# 4aw.net
KiCad netlist of a schematic drawn in EAGLE
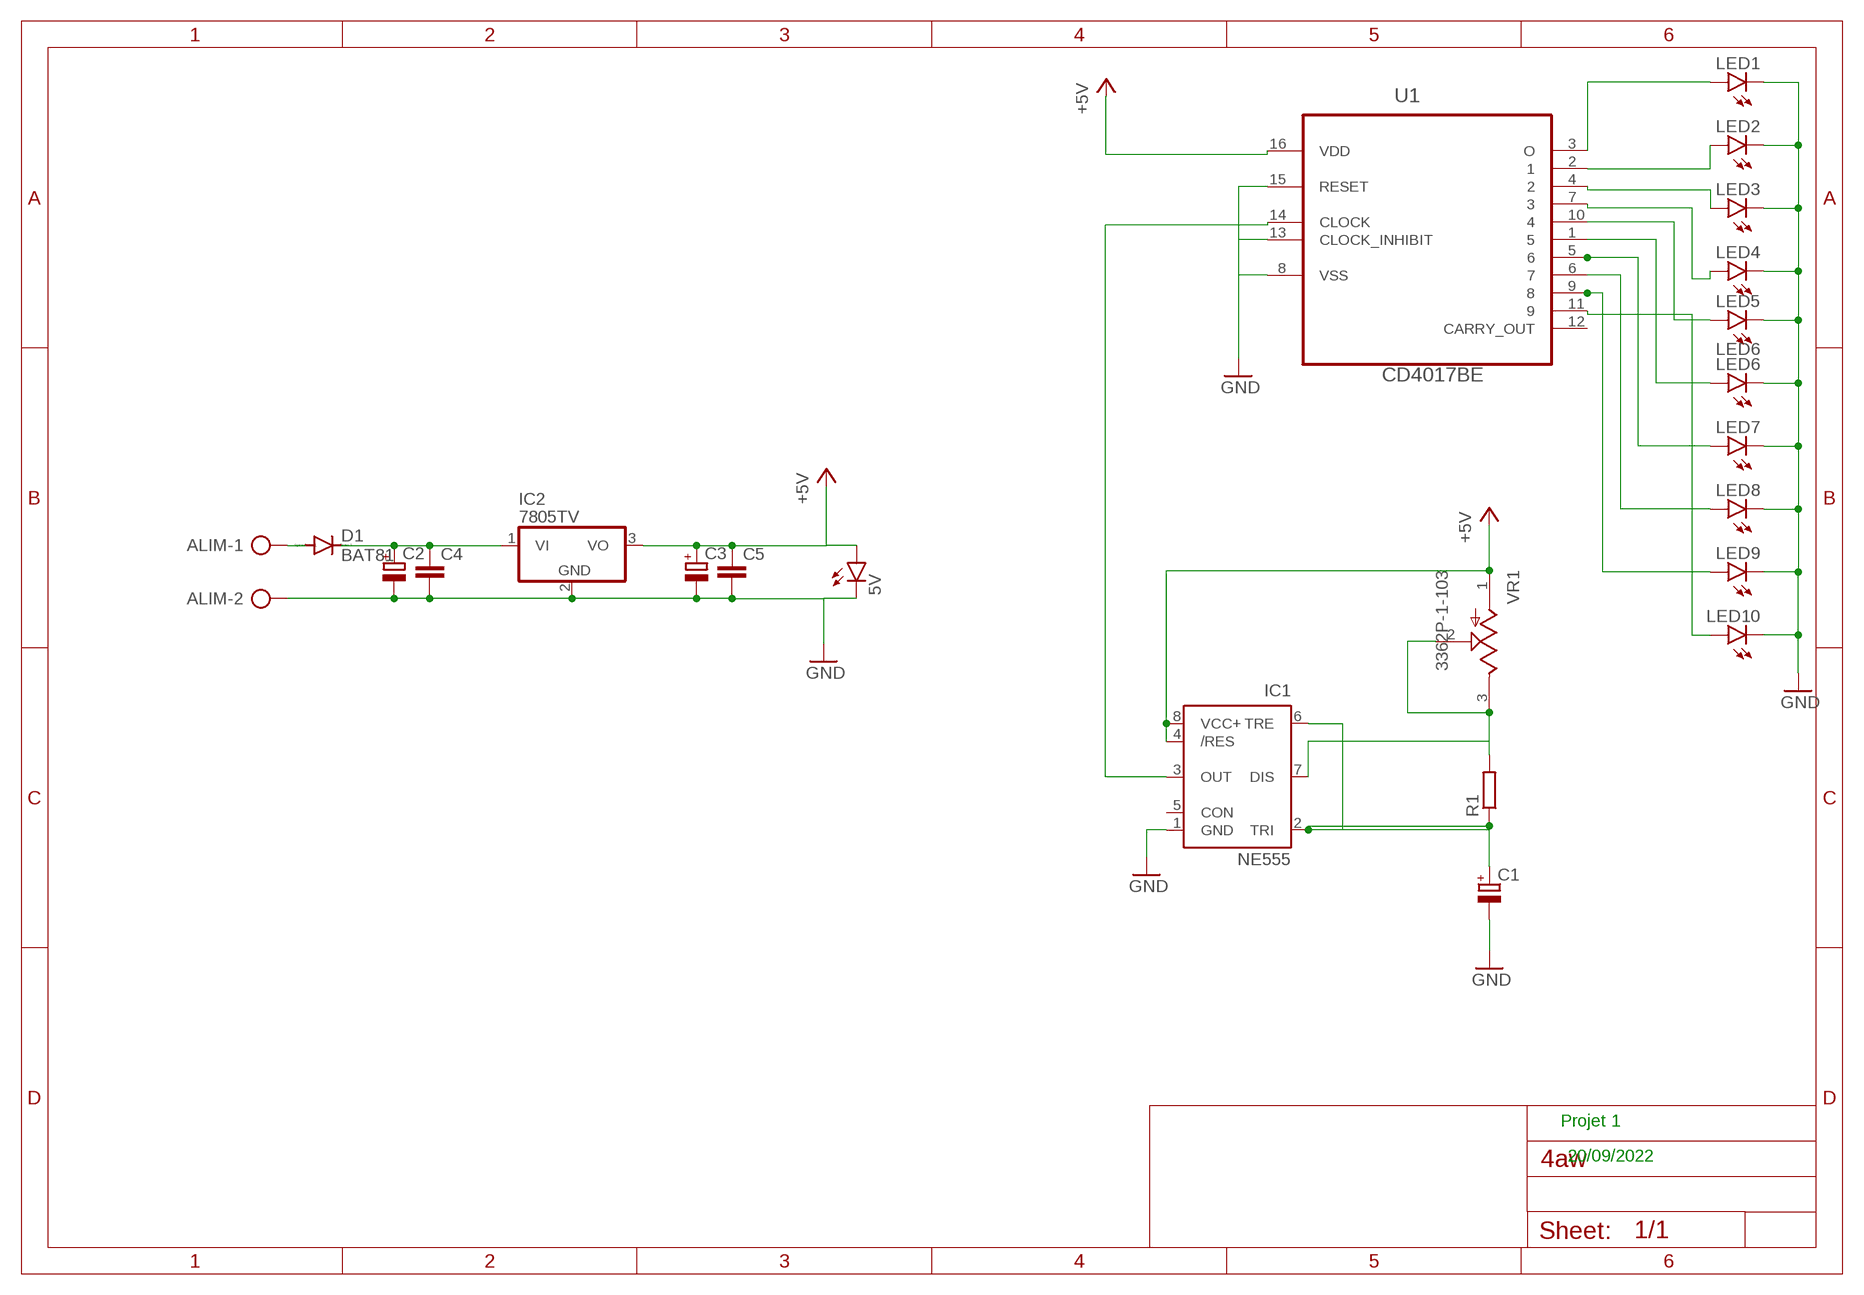
[diagram p0: schematic, sheet 1]

(export (version "E")
  (design (tool "Eeschema 10.0.6"))
  (components
    (comp (ref "5V")
      (value "LED3MM")
      (footprint "eagle-import:LED3MM")
      (libsource (lib "eagle-import") (part "LED3MM"))
    )
    (comp (ref "ALIM")
      (value "AK500/2")
      (footprint "eagle-import:AK500_2")
      (libsource (lib "eagle-import") (part "AK500/2"))
    )
    (comp (ref "C1")
      (value "CPOL-EUE2.5-5")
      (footprint "eagle-import:E2,5-5")
      (libsource (lib "eagle-import") (part "resistor_348_CPOL-EUE2.5-5"))
    )
    (comp (ref "C2")
      (value "CPOL-EUE2.5-5")
      (footprint "eagle-import:E2,5-5")
      (libsource (lib "eagle-import") (part "CPOL-EUE2.5-5"))
    )
    (comp (ref "C3")
      (value "CPOL-EUE2.5-5")
      (footprint "eagle-import:E2,5-5")
      (libsource (lib "eagle-import") (part "CPOL-EUE2.5-5"))
    )
    (comp (ref "C4")
      (value "C-EU050-024X044")
      (footprint "eagle-import:C050-024X044")
      (libsource (lib "eagle-import") (part "C-EU050-024X044"))
    )
    (comp (ref "C5")
      (value "C-EU050-024X044")
      (footprint "eagle-import:C050-024X044")
      (libsource (lib "eagle-import") (part "C-EU050-024X044"))
    )
    (comp (ref "D1")
      (value "BAT81")
      (footprint "eagle-import:DO34-7")
      (libsource (lib "eagle-import") (part "BAT81"))
    )
    (comp (ref "IC1")
      (value "NE555")
      (footprint "eagle-import:DIL-08")
      (fields (field (name "MF") "Arrow Electronics") (field (name "MPN") "NE555N"))
      (libsource (lib "eagle-import") (part "NE555"))
    )
    (comp (ref "IC2")
      (value "7805TV")
      (footprint "eagle-import:TO220V")
      (libsource (lib "eagle-import") (part "78TV05"))
    )
    (comp (ref "LED1")
      (value "LED5MM")
      (footprint "eagle-import:LED5MM")
      (libsource (lib "eagle-import") (part "LED5MM"))
    )
    (comp (ref "LED2")
      (value "LED5MM")
      (footprint "eagle-import:LED5MM")
      (libsource (lib "eagle-import") (part "LED5MM"))
    )
    (comp (ref "LED3")
      (value "LED5MM")
      (footprint "eagle-import:LED5MM")
      (libsource (lib "eagle-import") (part "LED5MM"))
    )
    (comp (ref "LED4")
      (value "LED5MM")
      (footprint "eagle-import:LED5MM")
      (libsource (lib "eagle-import") (part "LED5MM"))
    )
    (comp (ref "LED5")
      (value "LED5MM")
      (footprint "eagle-import:LED5MM")
      (libsource (lib "eagle-import") (part "LED5MM"))
    )
    (comp (ref "LED6")
      (value "LED6")
      (footprint "eagle-import:LED5MM")
      (libsource (lib "eagle-import") (part "LED5MM"))
    )
    (comp (ref "LED7")
      (value "LED5MM")
      (footprint "eagle-import:LED5MM")
      (libsource (lib "eagle-import") (part "LED5MM"))
    )
    (comp (ref "LED8")
      (value "LED5MM")
      (footprint "eagle-import:LED5MM")
      (libsource (lib "eagle-import") (part "LED5MM"))
    )
    (comp (ref "LED9")
      (value "LED5MM")
      (footprint "eagle-import:LED5MM")
      (libsource (lib "eagle-import") (part "LED5MM"))
    )
    (comp (ref "LED10")
      (value "LED5MM")
      (footprint "eagle-import:LED5MM")
      (libsource (lib "eagle-import") (part "LED5MM"))
    )
    (comp (ref "R1")
      (value "R-EU_0207/10")
      (footprint "eagle-import:0207_10")
      (libsource (lib "eagle-import") (part "R-EU_0207/10"))
    )
    (comp (ref "U1")
      (value "CD4017BE")
      (footprint "eagle-import:DIP254P762X508-16")
      (fields (field (name "MF") "Texas Instruments"))
      (libsource (lib "eagle-import") (part "CD4017BE"))
    )
    (comp (ref "VR1")
      (value "3362P-1-103")
      (footprint "eagle-import:TRIM_3362P-1-103")
      (fields (field (name "MF") "Bourns"))
      (libsource (lib "eagle-import") (part "3362P-1-103"))
    )
  )
  (nets
    (net (code "1") (name "+5V") (class "Default")
      (node (ref "5V") (pin "A") (pinfunction "A_A") (pintype "passive"))
      (node (ref "C3") (pin "+") (pinfunction "+_+") (pintype "passive"))
      (node (ref "C5") (pin "1") (pinfunction "1_1") (pintype "passive"))
      (node (ref "IC1") (pin "4") (pinfunction "/RES_4") (pintype "input"))
      (node (ref "IC1") (pin "8") (pinfunction "VCC+_8") (pintype "power_in"))
      (node (ref "IC2") (pin "3") (pinfunction "VO_3") (pintype "passive"))
      (node (ref "U1") (pin "16") (pinfunction "VDD_16") (pintype "power_in"))
      (node (ref "VR1") (pin "1") (pinfunction "CCW_1") (pintype "passive"))
    )
    (net (code "2") (name "GND") (class "Default")
      (node (ref "5V") (pin "K") (pinfunction "C_K") (pintype "passive"))
      (node (ref "ALIM") (pin "2") (pinfunction "KL_2") (pintype "passive"))
      (node (ref "C1") (pin "-") (pinfunction "-_-") (pintype "passive"))
      (node (ref "C2") (pin "-") (pinfunction "-_-") (pintype "passive"))
      (node (ref "C3") (pin "-") (pinfunction "-_-") (pintype "passive"))
      (node (ref "C4") (pin "2") (pinfunction "2_2") (pintype "passive"))
      (node (ref "C5") (pin "2") (pinfunction "2_2") (pintype "passive"))
      (node (ref "IC1") (pin "1") (pinfunction "GND_1") (pintype "power_in"))
      (node (ref "IC2") (pin "2") (pinfunction "GND_2") (pintype "passive"))
      (node (ref "LED1") (pin "K") (pinfunction "C_K") (pintype "passive"))
      (node (ref "LED10") (pin "K") (pinfunction "C_K") (pintype "passive"))
      (node (ref "LED2") (pin "K") (pinfunction "C_K") (pintype "passive"))
      (node (ref "LED3") (pin "K") (pinfunction "C_K") (pintype "passive"))
      (node (ref "LED4") (pin "K") (pinfunction "C_K") (pintype "passive"))
      (node (ref "LED5") (pin "K") (pinfunction "C_K") (pintype "passive"))
      (node (ref "LED6") (pin "K") (pinfunction "C_K") (pintype "passive"))
      (node (ref "LED7") (pin "K") (pinfunction "C_K") (pintype "passive"))
      (node (ref "LED8") (pin "K") (pinfunction "C_K") (pintype "passive"))
      (node (ref "LED9") (pin "K") (pinfunction "C_K") (pintype "passive"))
      (node (ref "U1") (pin "13") (pinfunction "CLOCK_INHIBIT_13") (pintype "input"))
      (node (ref "U1") (pin "15") (pinfunction "RESET_15") (pintype "input"))
      (node (ref "U1") (pin "8") (pinfunction "VSS_8") (pintype "power_in"))
    )
    (net (code "3") (name "Net-(ALIMA-KL)") (class "Default")
      (node (ref "ALIM") (pin "1") (pinfunction "KL_1") (pintype "passive"))
      (node (ref "D1") (pin "A") (pinfunction "A_A") (pintype "passive"))
    )
    (net (code "4") (name "Net-(IC1-DIS)") (class "Default")
      (node (ref "IC1") (pin "7") (pinfunction "DIS_7") (pintype "input"))
      (node (ref "R1") (pin "2") (pinfunction "2_2") (pintype "passive"))
      (node (ref "VR1") (pin "2") (pinfunction "WIPER_2") (pintype "passive"))
      (node (ref "VR1") (pin "3") (pinfunction "CW_3") (pintype "passive"))
    )
    (net (code "5") (name "Net-(IC1-OUT)") (class "Default")
      (node (ref "IC1") (pin "3") (pinfunction "OUT_3") (pintype "output"))
      (node (ref "U1") (pin "14") (pinfunction "CLOCK_14") (pintype "input"))
    )
    (net (code "6") (name "Net-(IC1-TRE)") (class "Default")
      (node (ref "C1") (pin "+") (pinfunction "+_+") (pintype "passive"))
      (node (ref "IC1") (pin "2") (pinfunction "TRI_2") (pintype "input"))
      (node (ref "IC1") (pin "6") (pinfunction "TRE_6") (pintype "input"))
      (node (ref "R1") (pin "1") (pinfunction "1_1") (pintype "passive"))
    )
    (net (code "7") (name "Net-(IC2-VI)") (class "Default")
      (node (ref "C2") (pin "+") (pinfunction "+_+") (pintype "passive"))
      (node (ref "C4") (pin "1") (pinfunction "1_1") (pintype "passive"))
      (node (ref "D1") (pin "C") (pinfunction "C_C") (pintype "passive"))
      (node (ref "IC2") (pin "1") (pinfunction "VI_1") (pintype "input"))
    )
    (net (code "8") (name "Net-(U1-1)") (class "Default")
      (node (ref "LED2") (pin "A") (pinfunction "A_A") (pintype "passive"))
      (node (ref "U1") (pin "2") (pinfunction "1_2") (pintype "output"))
    )
    (net (code "9") (name "Net-(U1-2)") (class "Default")
      (node (ref "LED3") (pin "A") (pinfunction "A_A") (pintype "passive"))
      (node (ref "U1") (pin "4") (pinfunction "2_4") (pintype "output"))
    )
    (net (code "10") (name "Net-(U1-3)") (class "Default")
      (node (ref "LED4") (pin "A") (pinfunction "A_A") (pintype "passive"))
      (node (ref "U1") (pin "7") (pinfunction "3_7") (pintype "output"))
    )
    (net (code "11") (name "Net-(U1-4)") (class "Default")
      (node (ref "LED5") (pin "A") (pinfunction "A_A") (pintype "passive"))
      (node (ref "U1") (pin "10") (pinfunction "4_10") (pintype "output"))
    )
    (net (code "12") (name "Net-(U1-5)") (class "Default")
      (node (ref "LED6") (pin "A") (pinfunction "A_A") (pintype "passive"))
      (node (ref "U1") (pin "1") (pinfunction "5_1") (pintype "output"))
    )
    (net (code "13") (name "Net-(U1-6)") (class "Default")
      (node (ref "LED7") (pin "A") (pinfunction "A_A") (pintype "passive"))
      (node (ref "U1") (pin "5") (pinfunction "6_5") (pintype "output"))
    )
    (net (code "14") (name "Net-(U1-7)") (class "Default")
      (node (ref "LED8") (pin "A") (pinfunction "A_A") (pintype "passive"))
      (node (ref "U1") (pin "6") (pinfunction "7_6") (pintype "output"))
    )
    (net (code "15") (name "Net-(U1-8)") (class "Default")
      (node (ref "LED9") (pin "A") (pinfunction "A_A") (pintype "passive"))
      (node (ref "U1") (pin "9") (pinfunction "8_9") (pintype "output"))
    )
    (net (code "16") (name "Net-(U1-9)") (class "Default")
      (node (ref "LED10") (pin "A") (pinfunction "A_A") (pintype "passive"))
      (node (ref "U1") (pin "11") (pinfunction "9_11") (pintype "output"))
    )
    (net (code "17") (name "Net-(U1-O)") (class "Default")
      (node (ref "LED1") (pin "A") (pinfunction "A_A") (pintype "passive"))
      (node (ref "U1") (pin "3") (pinfunction "O_3") (pintype "output"))
    )
    (net (code "18") (name "unconnected-(IC1-CON-Pad5)") (class "Default")
      (node (ref "IC1") (pin "5") (pinfunction "CON_5") (pintype "input"))
    )
    (net (code "19") (name "unconnected-(U1-CARRY_OUT-Pad12)") (class "Default")
      (node (ref "U1") (pin "12") (pinfunction "CARRY_OUT_12") (pintype "output"))
    )
  )
)
